# tilt_soms_lgbu_v3.net
KiCad netlist of a schematic drawn in EAGLE
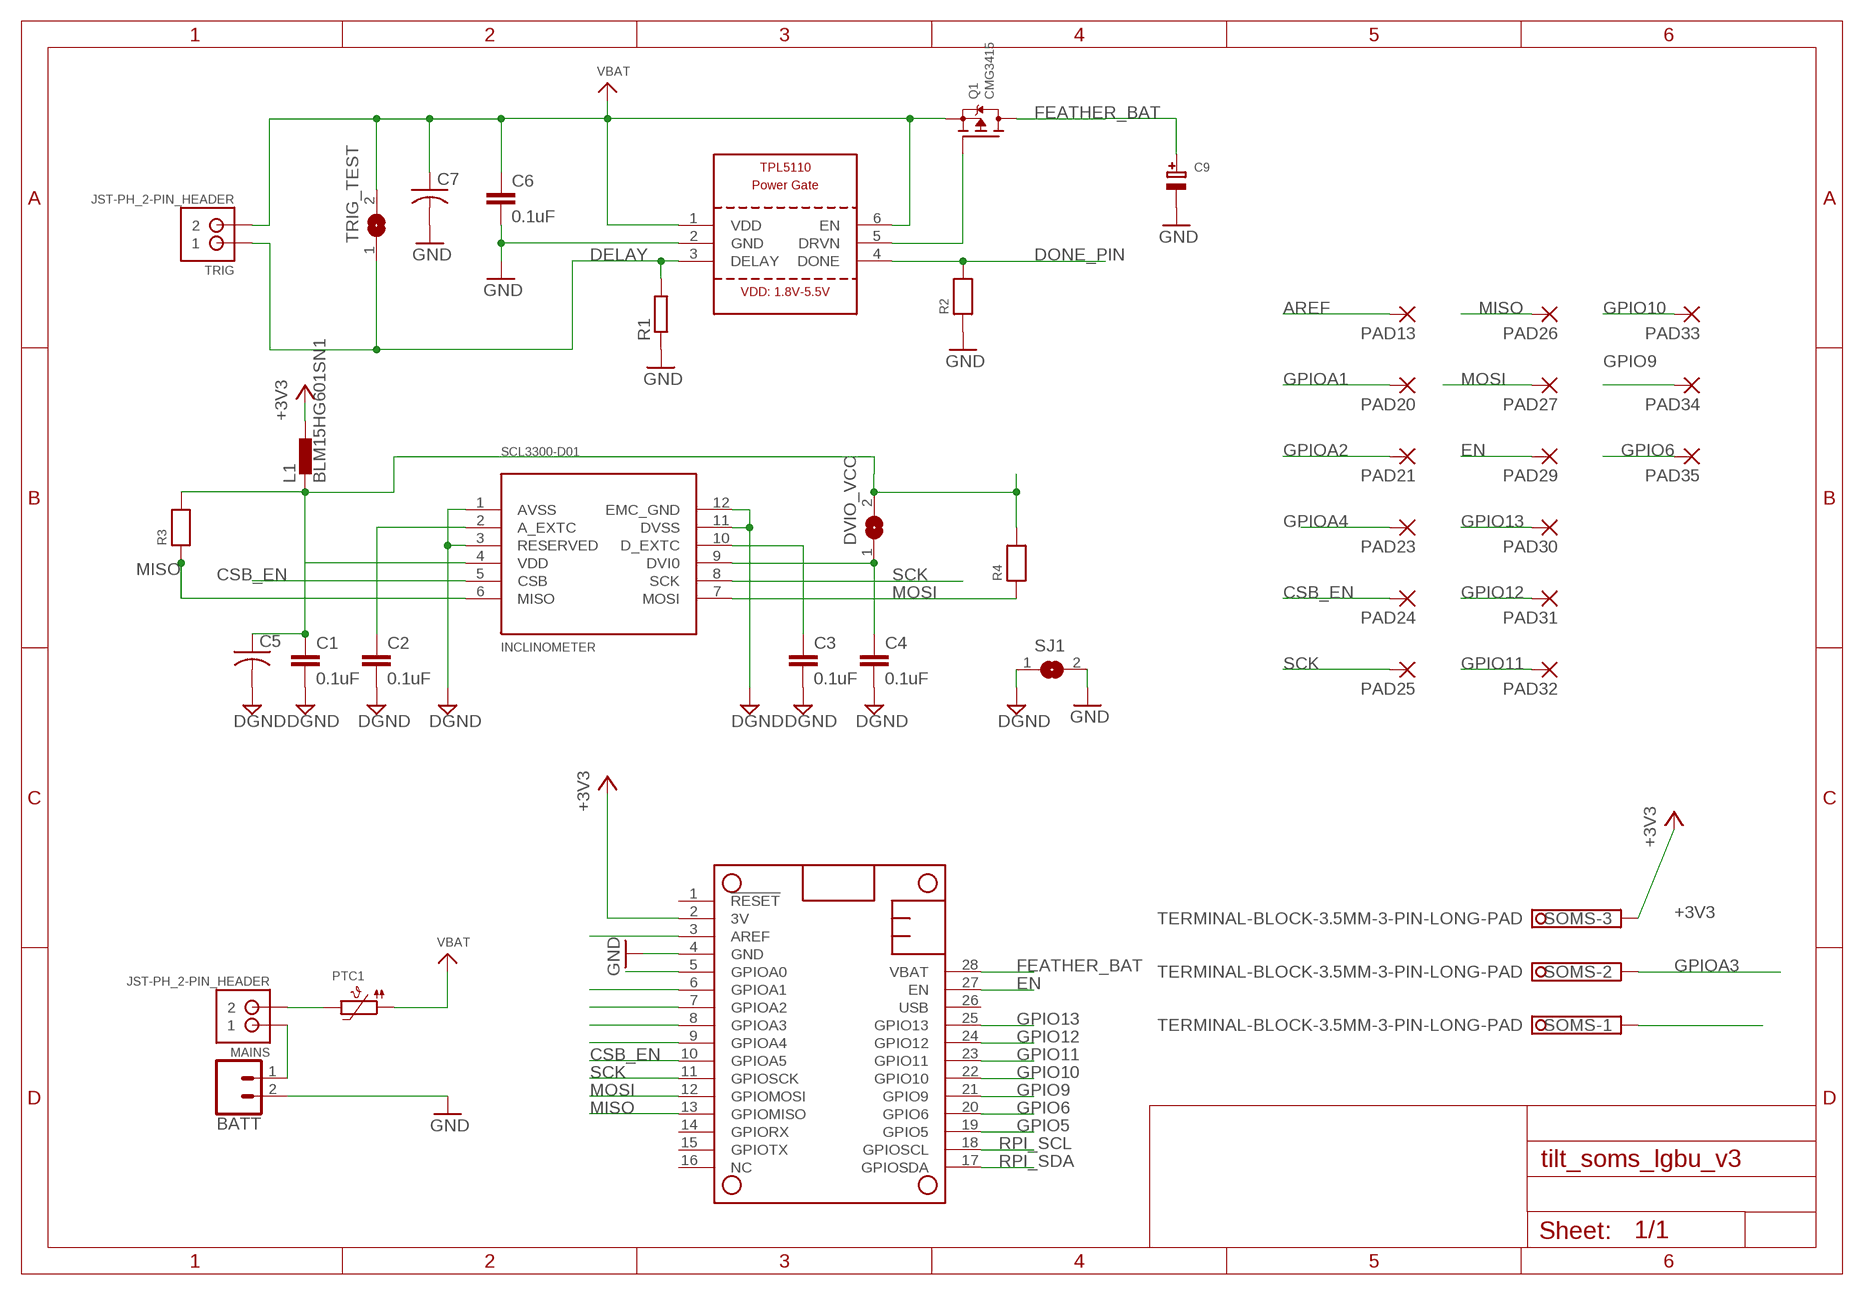
[diagram p0: schematic, sheet 1]

(export (version "E")
  (design (tool "Eeschema 10.0.6"))
  (components
    (comp (ref "BATT")
      (value "CONN_02POLAR_LOCK")
      (footprint "eagle-import:MOLEX-1X2_LOCK")
      (libsource (lib "eagle-import") (part "CONN_02POLAR_LOCK"))
    )
    (comp (ref "C1")
      (value "0.1uF")
      (footprint "eagle-import:C0402")
      (libsource (lib "eagle-import") (part "C-EUC0402"))
    )
    (comp (ref "C2")
      (value "0.1uF")
      (footprint "eagle-import:C0402")
      (libsource (lib "eagle-import") (part "C-EUC0402"))
    )
    (comp (ref "C3")
      (value "0.1uF")
      (footprint "eagle-import:C0402")
      (libsource (lib "eagle-import") (part "C-EUC0402"))
    )
    (comp (ref "C4")
      (value "0.1uF")
      (footprint "eagle-import:C0402")
      (libsource (lib "eagle-import") (part "C-EUC0402"))
    )
    (comp (ref "C5")
      (value "C-USC1206K")
      (footprint "eagle-import:C1206K")
      (libsource (lib "eagle-import") (part "C-USC1206K"))
    )
    (comp (ref "C6")
      (value "0.1uF")
      (footprint "eagle-import:C0402")
      (libsource (lib "eagle-import") (part "C-EUC0402"))
    )
    (comp (ref "C7")
      (value "C-USC1206K")
      (footprint "eagle-import:C1206K")
      (libsource (lib "eagle-import") (part "C-USC1206K"))
    )
    (comp (ref "C9")
      (value "CAP_TANTALUMA/3216_WAVE")
      (footprint "eagle-import:EIA3216-18_A-W")
      (libsource (lib "eagle-import") (part "CAP_TANTALUMA/3216_WAVE"))
    )
    (comp (ref "DVIO_VCC")
      (value "SOLDERJUMPER")
      (footprint "eagle-import:SOLDERJUMPER_ARROW_NOPASTE")
      (libsource (lib "eagle-import") (part "SOLDERJUMPER"))
    )
    (comp (ref "INCLINOMETER")
      (value "SCL3300-D01")
      (footprint "eagle-import:SCL3300-D01")
      (libsource (lib "eagle-import") (part "SCL3300-D01"))
    )
    (comp (ref "L1")
      (value "BLM15HG601SN1")
      (footprint "eagle-import:0402")
      (libsource (lib "eagle-import") (part "BLM15HG601SN1"))
    )
    (comp (ref "MAINS")
      (value "JST-PH_2-PIN_HEADER")
      (footprint "eagle-import:JST_B2B-PH_HEADER")
      (libsource (lib "eagle-import") (part "JST-PH_2-PIN_HEADER"))
    )
    (comp (ref "MS2")
      (value "FEATHERWINGFEATHERWING_EDC")
      (footprint "eagle-import:FEATHERWING_NODIM_HOLES_2")
      (libsource (lib "eagle-import") (part "FEATHERWINGFEATHERWING_EDC"))
    )
    (comp (ref "PAD13")
      (value "WIREPADSMD1,27-254")
      (footprint "eagle-import:SMD1,27-2,54")
      (libsource (lib "eagle-import") (part "WIREPADSMD1,27-254"))
    )
    (comp (ref "PAD20")
      (value "WIREPADSMD1,27-254")
      (footprint "eagle-import:SMD1,27-2,54")
      (libsource (lib "eagle-import") (part "WIREPADSMD1,27-254"))
    )
    (comp (ref "PAD21")
      (value "WIREPADSMD1,27-254")
      (footprint "eagle-import:SMD1,27-2,54")
      (libsource (lib "eagle-import") (part "WIREPADSMD1,27-254"))
    )
    (comp (ref "PAD23")
      (value "WIREPADSMD1,27-254")
      (footprint "eagle-import:SMD1,27-2,54")
      (libsource (lib "eagle-import") (part "WIREPADSMD1,27-254"))
    )
    (comp (ref "PAD24")
      (value "WIREPADSMD1,27-254")
      (footprint "eagle-import:SMD1,27-2,54")
      (libsource (lib "eagle-import") (part "WIREPADSMD1,27-254"))
    )
    (comp (ref "PAD25")
      (value "WIREPADSMD1,27-254")
      (footprint "eagle-import:SMD1,27-2,54")
      (libsource (lib "eagle-import") (part "WIREPADSMD1,27-254"))
    )
    (comp (ref "PAD26")
      (value "WIREPADSMD1,27-254")
      (footprint "eagle-import:SMD1,27-2,54")
      (libsource (lib "eagle-import") (part "WIREPADSMD1,27-254"))
    )
    (comp (ref "PAD27")
      (value "WIREPADSMD1,27-254")
      (footprint "eagle-import:SMD1,27-2,54")
      (libsource (lib "eagle-import") (part "WIREPADSMD1,27-254"))
    )
    (comp (ref "PAD29")
      (value "WIREPADSMD1,27-254")
      (footprint "eagle-import:SMD1,27-2,54")
      (libsource (lib "eagle-import") (part "WIREPADSMD1,27-254"))
    )
    (comp (ref "PAD30")
      (value "WIREPADSMD1,27-254")
      (footprint "eagle-import:SMD1,27-2,54")
      (libsource (lib "eagle-import") (part "WIREPADSMD1,27-254"))
    )
    (comp (ref "PAD31")
      (value "WIREPADSMD1,27-254")
      (footprint "eagle-import:SMD1,27-2,54")
      (libsource (lib "eagle-import") (part "WIREPADSMD1,27-254"))
    )
    (comp (ref "PAD32")
      (value "WIREPADSMD1,27-254")
      (footprint "eagle-import:SMD1,27-2,54")
      (libsource (lib "eagle-import") (part "WIREPADSMD1,27-254"))
    )
    (comp (ref "PAD33")
      (value "WIREPADSMD1,27-254")
      (footprint "eagle-import:SMD1,27-2,54")
      (libsource (lib "eagle-import") (part "WIREPADSMD1,27-254"))
    )
    (comp (ref "PAD34")
      (value "WIREPADSMD1,27-254")
      (footprint "eagle-import:SMD1,27-2,54")
      (libsource (lib "eagle-import") (part "WIREPADSMD1,27-254"))
    )
    (comp (ref "PAD35")
      (value "WIREPADSMD1,27-254")
      (footprint "eagle-import:SMD1,27-2,54")
      (libsource (lib "eagle-import") (part "WIREPADSMD1,27-254"))
    )
    (comp (ref "PTC1")
      (value "PTC1210")
      (footprint "eagle-import:PTC1210")
      (libsource (lib "eagle-import") (part "PTC1210"))
    )
    (comp (ref "Q1")
      (value "CMG3415")
      (footprint "eagle-import:SOT23-WIDE")
      (libsource (lib "eagle-import") (part "MOSFET-PWIDE"))
    )
    (comp (ref "R1")
      (value "R-EU_0207/10")
      (footprint "eagle-import:0207_10")
      (libsource (lib "eagle-import") (part "R-EU_0207/10"))
    )
    (comp (ref "R2")
      (value "RESISTOR0805")
      (footprint "eagle-import:0805")
      (libsource (lib "eagle-import") (part "RESISTOR0805"))
    )
    (comp (ref "R3")
      (value "RESISTOR0805")
      (footprint "eagle-import:0805")
      (libsource (lib "eagle-import") (part "RESISTOR0805"))
    )
    (comp (ref "R4")
      (value "RESISTOR0805")
      (footprint "eagle-import:0805")
      (libsource (lib "eagle-import") (part "RESISTOR0805"))
    )
    (comp (ref "SJ1") (value "SJ") (footprint "eagle-import:SJ") (libsource (lib "eagle-import") (part "SJ")))
    (comp (ref "SOMS")
      (value "TERMINAL-BLOCK-3.5MM-3-PIN-LONG-PAD")
      (footprint "eagle-import:TERMINAL-BLOCK-3-PIN-3.5MM-LONG-PAD")
      (libsource (lib "eagle-import") (part "TERMINAL-BLOCK-3.5MM-3-PIN-LONG-PAD"))
    )
    (comp (ref "TIMER")
      (value "TPL5110")
      (footprint "eagle-import:SOT23-6")
      (libsource (lib "eagle-import") (part "TPL5110"))
    )
    (comp (ref "TRIG")
      (value "JST-PH_2-PIN_HEADER")
      (footprint "eagle-import:JST_B2B-PH_HEADER")
      (libsource (lib "eagle-import") (part "JST-PH_2-PIN_HEADER"))
    )
    (comp (ref "TRIG_TEST")
      (value "SOLDERJUMPER")
      (footprint "eagle-import:SOLDERJUMPER_ARROW_NOPASTE")
      (libsource (lib "eagle-import") (part "SOLDERJUMPER"))
    )
  )
  (nets
    (net (code "1") (name "+3V3") (class "Default")
      (node (ref "L1") (pin "2") (pinfunction "2_2") (pintype "passive"))
      (node (ref "MS2") (pin "2") (pinfunction "3V_2") (pintype "power_in"))
      (node (ref "SOMS") (pin "3") (pinfunction "K_3") (pintype "passive"))
    )
    (net (code "2") (name "/AREF") (class "Default")
      (node (ref "MS2") (pin "3") (pinfunction "AREF_3") (pintype "passive"))
      (node (ref "PAD13") (pin "1") (pinfunction "P_1") (pintype "passive"))
    )
    (net (code "3") (name "/CSB_EN") (class "Default")
      (node (ref "INCLINOMETER") (pin "5") (pinfunction "CSB_5") (pintype "bidirectional"))
      (node (ref "MS2") (pin "10") (pinfunction "GPIOA5_10") (pintype "bidirectional"))
      (node (ref "PAD24") (pin "1") (pinfunction "P_1") (pintype "passive"))
    )
    (net (code "4") (name "/DELAY") (class "Default")
      (node (ref "R1") (pin "2") (pinfunction "2_2") (pintype "passive"))
      (node (ref "TIMER") (pin "3") (pinfunction "DELAY_3") (pintype "bidirectional"))
      (node (ref "TRIG") (pin "P1") (pinfunction "1_P1") (pintype "bidirectional"))
      (node (ref "TRIG_TEST") (pin "1") (pinfunction "1_1") (pintype "passive"))
    )
    (net (code "5") (name "/DONE_PIN") (class "Default")
      (node (ref "MS2") (pin "5") (pinfunction "GPIOA0_5") (pintype "bidirectional"))
      (node (ref "R2") (pin "2") (pinfunction "2_2") (pintype "passive"))
      (node (ref "TIMER") (pin "4") (pinfunction "DONE_4") (pintype "bidirectional"))
    )
    (net (code "6") (name "/EN") (class "Default")
      (node (ref "MS2") (pin "27") (pinfunction "EN_27") (pintype "passive"))
      (node (ref "PAD29") (pin "1") (pinfunction "P_1") (pintype "passive"))
    )
    (net (code "7") (name "/FEATHER_BAT") (class "Default")
      (node (ref "C9") (pin "+") (pinfunction "+_+") (pintype "passive"))
      (node (ref "MS2") (pin "28") (pinfunction "VBAT_28") (pintype "power_in"))
      (node (ref "Q1") (pin "3") (pinfunction "D_3") (pintype "passive"))
    )
    (net (code "8") (name "/GPIO5") (class "Default")
      (node (ref "MS2") (pin "19") (pinfunction "GPIO5_19") (pintype "bidirectional"))
    )
    (net (code "9") (name "/GPIO6") (class "Default")
      (node (ref "MS2") (pin "20") (pinfunction "GPIO6_20") (pintype "bidirectional"))
      (node (ref "PAD35") (pin "1") (pinfunction "P_1") (pintype "passive"))
    )
    (net (code "10") (name "/GPIO9") (class "Default")
      (node (ref "MS2") (pin "21") (pinfunction "GPIO9_21") (pintype "bidirectional"))
      (node (ref "PAD34") (pin "1") (pinfunction "P_1") (pintype "passive"))
    )
    (net (code "11") (name "/GPIO10") (class "Default")
      (node (ref "MS2") (pin "22") (pinfunction "GPIO10_22") (pintype "bidirectional"))
      (node (ref "PAD33") (pin "1") (pinfunction "P_1") (pintype "passive"))
    )
    (net (code "12") (name "/GPIO11") (class "Default")
      (node (ref "MS2") (pin "23") (pinfunction "GPIO11_23") (pintype "bidirectional"))
      (node (ref "PAD32") (pin "1") (pinfunction "P_1") (pintype "passive"))
    )
    (net (code "13") (name "/GPIO12") (class "Default")
      (node (ref "MS2") (pin "24") (pinfunction "GPIO12_24") (pintype "bidirectional"))
      (node (ref "PAD31") (pin "1") (pinfunction "P_1") (pintype "passive"))
    )
    (net (code "14") (name "/GPIO13") (class "Default")
      (node (ref "MS2") (pin "25") (pinfunction "GPIO13_25") (pintype "bidirectional"))
      (node (ref "PAD30") (pin "1") (pinfunction "P_1") (pintype "passive"))
    )
    (net (code "15") (name "/GPIOA1") (class "Default")
      (node (ref "MS2") (pin "6") (pinfunction "GPIOA1_6") (pintype "bidirectional"))
      (node (ref "PAD20") (pin "1") (pinfunction "P_1") (pintype "passive"))
    )
    (net (code "16") (name "/GPIOA2") (class "Default")
      (node (ref "MS2") (pin "7") (pinfunction "GPIOA2_7") (pintype "bidirectional"))
      (node (ref "PAD21") (pin "1") (pinfunction "P_1") (pintype "passive"))
    )
    (net (code "17") (name "/GPIOA3") (class "Default")
      (node (ref "MS2") (pin "8") (pinfunction "GPIOA3_8") (pintype "bidirectional"))
      (node (ref "SOMS") (pin "2") (pinfunction "K_2") (pintype "passive"))
    )
    (net (code "18") (name "/GPIOA4") (class "Default")
      (node (ref "MS2") (pin "9") (pinfunction "GPIOA4_9") (pintype "bidirectional"))
      (node (ref "PAD23") (pin "1") (pinfunction "P_1") (pintype "passive"))
    )
    (net (code "19") (name "/MISO") (class "Default")
      (node (ref "INCLINOMETER") (pin "6") (pinfunction "MISO_6") (pintype "bidirectional"))
      (node (ref "MS2") (pin "13") (pinfunction "GPIOMISO_13") (pintype "bidirectional"))
      (node (ref "PAD26") (pin "1") (pinfunction "P_1") (pintype "passive"))
      (node (ref "R3") (pin "1") (pinfunction "1_1") (pintype "passive"))
    )
    (net (code "20") (name "/MOSI") (class "Default")
      (node (ref "INCLINOMETER") (pin "7") (pinfunction "MOSI_7") (pintype "bidirectional"))
      (node (ref "MS2") (pin "12") (pinfunction "GPIOMOSI_12") (pintype "bidirectional"))
      (node (ref "PAD27") (pin "1") (pinfunction "P_1") (pintype "passive"))
      (node (ref "R4") (pin "1") (pinfunction "1_1") (pintype "passive"))
    )
    (net (code "21") (name "/RPI_SCL") (class "Default")
      (node (ref "MS2") (pin "18") (pinfunction "GPIOSCL_18") (pintype "bidirectional"))
    )
    (net (code "22") (name "/RPI_SDA") (class "Default")
      (node (ref "MS2") (pin "17") (pinfunction "GPIOSDA_17") (pintype "bidirectional"))
    )
    (net (code "23") (name "/SCK") (class "Default")
      (node (ref "INCLINOMETER") (pin "8") (pinfunction "SCK_8") (pintype "bidirectional"))
      (node (ref "MS2") (pin "11") (pinfunction "GPIOSCK_11") (pintype "bidirectional"))
      (node (ref "PAD25") (pin "1") (pinfunction "P_1") (pintype "passive"))
    )
    (net (code "24") (name "/USB") (class "Default")
      (node (ref "MS2") (pin "26") (pinfunction "USB_26") (pintype "power_in"))
    )
    (net (code "25") (name "DGND") (class "Default")
      (node (ref "C1") (pin "2") (pinfunction "2_2") (pintype "passive"))
      (node (ref "C2") (pin "2") (pinfunction "2_2") (pintype "passive"))
      (node (ref "C3") (pin "2") (pinfunction "2_2") (pintype "passive"))
      (node (ref "C4") (pin "2") (pinfunction "2_2") (pintype "passive"))
      (node (ref "C5") (pin "2") (pinfunction "2_2") (pintype "passive"))
      (node (ref "INCLINOMETER") (pin "1") (pinfunction "AVSS_1") (pintype "bidirectional"))
      (node (ref "INCLINOMETER") (pin "11") (pinfunction "DVSS_11") (pintype "bidirectional"))
      (node (ref "INCLINOMETER") (pin "12") (pinfunction "EMC_GND_12") (pintype "bidirectional"))
      (node (ref "INCLINOMETER") (pin "3") (pinfunction "RESERVED_3") (pintype "bidirectional"))
      (node (ref "SJ1") (pin "1") (pinfunction "1_1") (pintype "passive"))
    )
    (net (code "26") (name "GND") (class "Default")
      (node (ref "BATT") (pin "2") (pinfunction "2_2") (pintype "passive"))
      (node (ref "C6") (pin "2") (pinfunction "2_2") (pintype "passive"))
      (node (ref "C7") (pin "2") (pinfunction "2_2") (pintype "passive"))
      (node (ref "C9") (pin "-") (pinfunction "-_-") (pintype "passive"))
      (node (ref "MS2") (pin "4") (pinfunction "GND_4") (pintype "power_in"))
      (node (ref "R1") (pin "1") (pinfunction "1_1") (pintype "passive"))
      (node (ref "R2") (pin "1") (pinfunction "1_1") (pintype "passive"))
      (node (ref "SJ1") (pin "2") (pinfunction "2_2") (pintype "passive"))
      (node (ref "SOMS") (pin "1") (pinfunction "K_1") (pintype "passive"))
      (node (ref "TIMER") (pin "2") (pinfunction "GND_2") (pintype "bidirectional"))
    )
    (net (code "27") (name "Net-(INCLINOMETER-A_EXTC)") (class "Default")
      (node (ref "C2") (pin "1") (pinfunction "1_1") (pintype "passive"))
      (node (ref "INCLINOMETER") (pin "2") (pinfunction "A_EXTC_2") (pintype "bidirectional"))
    )
    (net (code "28") (name "Net-(INCLINOMETER-DVI0)") (class "Default")
      (node (ref "C4") (pin "1") (pinfunction "1_1") (pintype "passive"))
      (node (ref "DVIO_VCC") (pin "1") (pinfunction "1_1") (pintype "passive"))
      (node (ref "INCLINOMETER") (pin "9") (pinfunction "DVI0_9") (pintype "bidirectional"))
    )
    (net (code "29") (name "Net-(INCLINOMETER-D_EXTC)") (class "Default")
      (node (ref "C3") (pin "1") (pinfunction "1_1") (pintype "passive"))
      (node (ref "INCLINOMETER") (pin "10") (pinfunction "D_EXTC_10") (pintype "bidirectional"))
    )
    (net (code "30") (name "Net-(INCLINOMETER-VDD)") (class "Default")
      (node (ref "C1") (pin "1") (pinfunction "1_1") (pintype "passive"))
      (node (ref "C5") (pin "1") (pinfunction "1_1") (pintype "passive"))
      (node (ref "DVIO_VCC") (pin "2") (pinfunction "2_2") (pintype "passive"))
      (node (ref "INCLINOMETER") (pin "4") (pinfunction "VDD_4") (pintype "bidirectional"))
      (node (ref "L1") (pin "1") (pinfunction "1_1") (pintype "passive"))
      (node (ref "R3") (pin "2") (pinfunction "2_2") (pintype "passive"))
      (node (ref "R4") (pin "2") (pinfunction "2_2") (pintype "passive"))
    )
    (net (code "31") (name "Net-(MAINS-1)") (class "Default")
      (node (ref "BATT") (pin "1") (pinfunction "1_1") (pintype "passive"))
      (node (ref "MAINS") (pin "P1") (pinfunction "1_P1") (pintype "bidirectional"))
    )
    (net (code "32") (name "Net-(MAINS-2)") (class "Default")
      (node (ref "MAINS") (pin "P2") (pinfunction "2_P2") (pintype "bidirectional"))
      (node (ref "PTC1") (pin "P$2") (pinfunction "2_P$2") (pintype "passive"))
    )
    (net (code "33") (name "Net-(Q1-G)") (class "Default")
      (node (ref "Q1") (pin "1") (pinfunction "G_1") (pintype "passive"))
      (node (ref "TIMER") (pin "5") (pinfunction "DRVN_5") (pintype "bidirectional"))
    )
    (net (code "34") (name "VBAT") (class "Default")
      (node (ref "C6") (pin "1") (pinfunction "1_1") (pintype "passive"))
      (node (ref "C7") (pin "1") (pinfunction "1_1") (pintype "passive"))
      (node (ref "PTC1") (pin "P$1") (pinfunction "1_P$1") (pintype "passive"))
      (node (ref "Q1") (pin "2") (pinfunction "S_2") (pintype "passive"))
      (node (ref "TIMER") (pin "1") (pinfunction "VDD_1") (pintype "bidirectional"))
      (node (ref "TIMER") (pin "6") (pinfunction "EN_6") (pintype "bidirectional"))
      (node (ref "TRIG") (pin "P2") (pinfunction "2_P2") (pintype "bidirectional"))
      (node (ref "TRIG_TEST") (pin "2") (pinfunction "2_2") (pintype "passive"))
    )
    (net (code "35") (name "unconnected-(MS2-GPIORX-Pad14)") (class "Default")
      (node (ref "MS2") (pin "14") (pinfunction "GPIORX_14") (pintype "bidirectional"))
    )
    (net (code "36") (name "unconnected-(MS2-GPIOTX-Pad15)") (class "Default")
      (node (ref "MS2") (pin "15") (pinfunction "GPIOTX_15") (pintype "bidirectional"))
    )
    (net (code "37") (name "unconnected-(MS2-NC-Pad16)") (class "Default")
      (node (ref "MS2") (pin "16") (pinfunction "NC_16") (pintype "passive"))
    )
    (net (code "38") (name "unconnected-(MS2-~{RESET}-Pad1)") (class "Default")
      (node (ref "MS2") (pin "1") (pinfunction "~{RESET}_1") (pintype "input"))
    )
  )
)
